# prj3.net
KiCad netlist of a schematic drawn in EAGLE
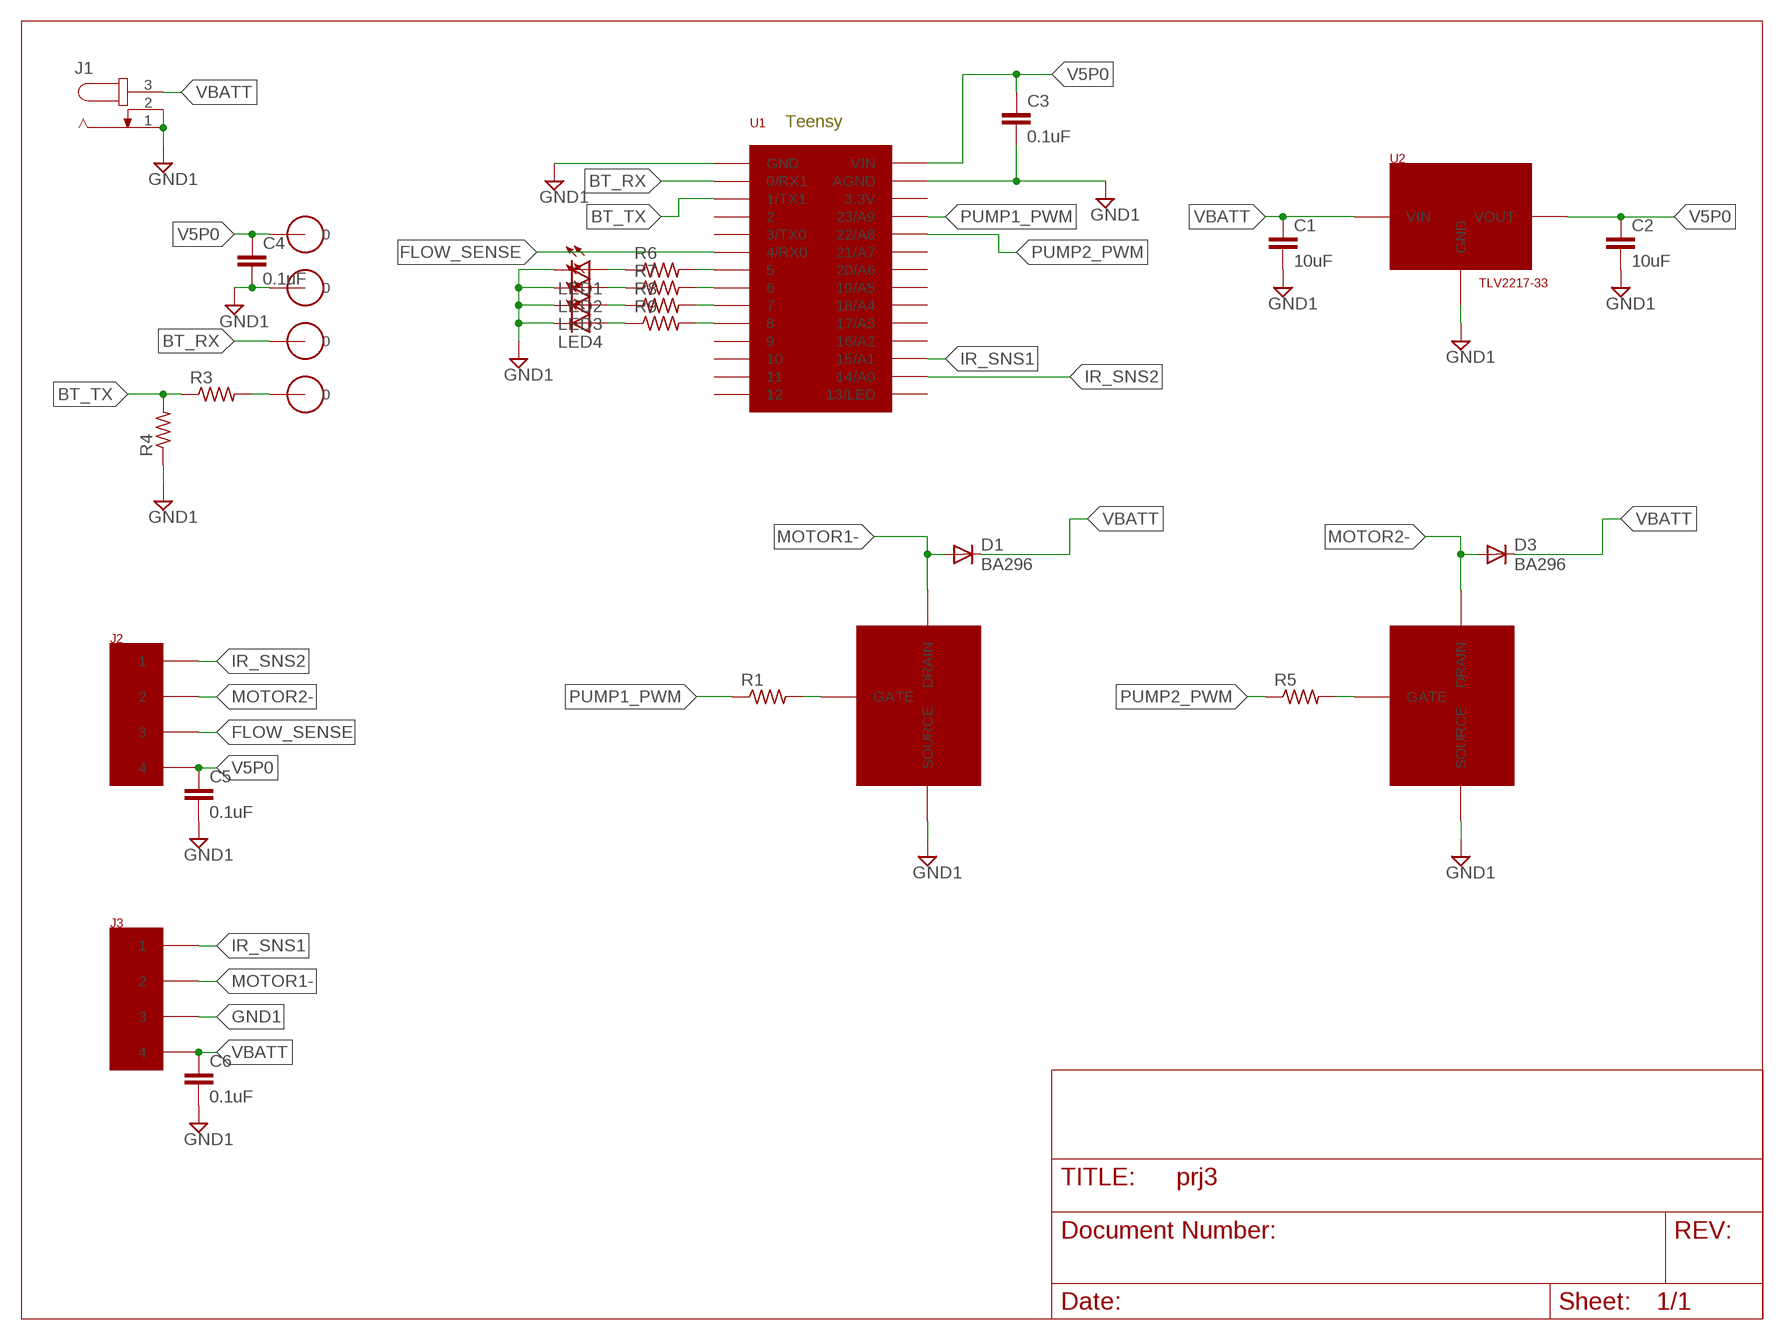
[diagram p0: schematic, sheet 1]

(export (version "E")
  (design (tool "Eeschema 10.0.6"))
  (components
    (comp (ref "C1")
      (value "10uF")
      (footprint "eagle-import:C2.5-3")
      (libsource (lib "eagle-import") (part "C2,5-3"))
    )
    (comp (ref "C2")
      (value "10uF")
      (footprint "eagle-import:C2.5-3")
      (libsource (lib "eagle-import") (part "C2,5-3"))
    )
    (comp (ref "C3")
      (value "0.1uF")
      (footprint "eagle-import:C2.5-3")
      (libsource (lib "eagle-import") (part "C2,5-3"))
    )
    (comp (ref "C4")
      (value "0.1uF")
      (footprint "eagle-import:C2.5-3")
      (libsource (lib "eagle-import") (part "C2,5-3"))
    )
    (comp (ref "C5")
      (value "0.1uF")
      (footprint "eagle-import:C2.5-3")
      (libsource (lib "eagle-import") (part "C2,5-3"))
    )
    (comp (ref "C6")
      (value "0.1uF")
      (footprint "eagle-import:C2.5-3")
      (libsource (lib "eagle-import") (part "C2,5-3"))
    )
    (comp (ref "D1")
      (value "BA296")
      (footprint "eagle-import:P2-15")
      (libsource (lib "eagle-import") (part "BA296"))
    )
    (comp (ref "D3")
      (value "BA296")
      (footprint "eagle-import:P2-15")
      (libsource (lib "eagle-import") (part "BA296"))
    )
    (comp (ref "J1")
      (value "JACK-PLUG0")
      (footprint "eagle-import:SPC4077")
      (libsource (lib "eagle-import") (part "JACK-PLUG0"))
    )
    (comp (ref "J2")
      (value "1776119-4")
      (footprint "eagle-import:4P_SCREW_TERMINAL")
      (libsource (lib "eagle-import") (part "1776119-4"))
    )
    (comp (ref "J3")
      (value "1776119-4")
      (footprint "eagle-import:4P_SCREW_TERMINAL")
      (libsource (lib "eagle-import") (part "1776119-4"))
    )
    (comp (ref "J7")
      (value "35MIL_HOLE")
      (footprint "eagle-import:35MIL_HOLE")
      (libsource (lib "eagle-import") (part "35MIL_HOLE"))
    )
    (comp (ref "J8")
      (value "35MIL_HOLE")
      (footprint "eagle-import:35MIL_HOLE")
      (libsource (lib "eagle-import") (part "35MIL_HOLE"))
    )
    (comp (ref "J9")
      (value "35MIL_HOLE")
      (footprint "eagle-import:35MIL_HOLE")
      (libsource (lib "eagle-import") (part "35MIL_HOLE"))
    )
    (comp (ref "J10")
      (value "35MIL_HOLE")
      (footprint "eagle-import:35MIL_HOLE")
      (libsource (lib "eagle-import") (part "35MIL_HOLE"))
    )
    (comp (ref "LED1")
      (value "LED_ELD260")
      (footprint "eagle-import:LED_LD260")
      (libsource (lib "eagle-import") (part "LED_ELD260"))
    )
    (comp (ref "LED2")
      (value "LED_ELD260")
      (footprint "eagle-import:LED_LD260")
      (libsource (lib "eagle-import") (part "LED_ELD260"))
    )
    (comp (ref "LED3")
      (value "LED_ELD260")
      (footprint "eagle-import:LED_LD260")
      (libsource (lib "eagle-import") (part "LED_ELD260"))
    )
    (comp (ref "LED4")
      (value "LED_ELD260")
      (footprint "eagle-import:LED_LD260")
      (libsource (lib "eagle-import") (part "LED_ELD260"))
    )
    (comp (ref "R1")
      (value "R-US_0207/10")
      (footprint "eagle-import:0207_10")
      (libsource (lib "eagle-import") (part "R-US_0207/10"))
    )
    (comp (ref "R3")
      (value "R-US_0207/10")
      (footprint "eagle-import:0207_10")
      (libsource (lib "eagle-import") (part "R-US_0207/10"))
    )
    (comp (ref "R4")
      (value "R-US_0207/10")
      (footprint "eagle-import:0207_10")
      (libsource (lib "eagle-import") (part "R-US_0207/10"))
    )
    (comp (ref "R5")
      (value "R-US_0207/10")
      (footprint "eagle-import:0207_10")
      (libsource (lib "eagle-import") (part "R-US_0207/10"))
    )
    (comp (ref "R6")
      (value "R-US_0207/10")
      (footprint "eagle-import:0207_10")
      (libsource (lib "eagle-import") (part "R-US_0207/10"))
    )
    (comp (ref "R7")
      (value "R-US_0207/10")
      (footprint "eagle-import:0207_10")
      (libsource (lib "eagle-import") (part "R-US_0207/10"))
    )
    (comp (ref "R8")
      (value "R-US_0207/10")
      (footprint "eagle-import:0207_10")
      (libsource (lib "eagle-import") (part "R-US_0207/10"))
    )
    (comp (ref "R9")
      (value "R-US_0207/10")
      (footprint "eagle-import:0207_10")
      (libsource (lib "eagle-import") (part "R-US_0207/10"))
    )
    (comp (ref "U$2")
      (value "NFET")
      (footprint "eagle-import:TO-220")
      (libsource (lib "eagle-import") (part "NFET"))
    )
    (comp (ref "U$3")
      (value "NFET")
      (footprint "eagle-import:TO-220")
      (libsource (lib "eagle-import") (part "NFET"))
    )
    (comp (ref "U1")
      (value "TEENSY")
      (footprint "eagle-import:TEENSY")
      (libsource (lib "eagle-import") (part "TEENSY"))
    )
    (comp (ref "U2")
      (value "TLV2217-33")
      (footprint "eagle-import:TO-220")
      (libsource (lib "eagle-import") (part "TLV2217-33"))
    )
  )
  (nets
    (net (code "1") (name "BT_RX") (class "Default")
      (node (ref "J9") (pin "P$1") (pinfunction "0_P$1") (pintype "bidirectional"))
      (node (ref "U1") (pin "P$2") (pinfunction "0/RX1_P$2") (pintype "bidirectional"))
    )
    (net (code "2") (name "BT_TX") (class "Default")
      (node (ref "R3") (pin "1") (pinfunction "1_1") (pintype "passive"))
      (node (ref "R4") (pin "2") (pinfunction "2_2") (pintype "passive"))
      (node (ref "U1") (pin "P$3") (pinfunction "1/TX1_P$3") (pintype "bidirectional"))
    )
    (net (code "3") (name "FLOW_SENSE") (class "Default")
      (node (ref "J2") (pin "P$3") (pinfunction "3_P$3") (pintype "bidirectional"))
      (node (ref "U1") (pin "P$6") (pinfunction "4/RX0_P$6") (pintype "bidirectional"))
    )
    (net (code "4") (name "GND1") (class "Default")
      (node (ref "C1") (pin "2") (pinfunction "2_2") (pintype "passive"))
      (node (ref "C2") (pin "2") (pinfunction "2_2") (pintype "passive"))
      (node (ref "C3") (pin "2") (pinfunction "2_2") (pintype "passive"))
      (node (ref "C4") (pin "2") (pinfunction "2_2") (pintype "passive"))
      (node (ref "C5") (pin "2") (pinfunction "2_2") (pintype "passive"))
      (node (ref "C6") (pin "2") (pinfunction "2_2") (pintype "passive"))
      (node (ref "J1") (pin "1") (pinfunction "1_1") (pintype "passive"))
      (node (ref "J1") (pin "2") (pinfunction "2_2") (pintype "passive"))
      (node (ref "J3") (pin "P$3") (pinfunction "3_P$3") (pintype "bidirectional"))
      (node (ref "J8") (pin "P$1") (pinfunction "0_P$1") (pintype "bidirectional"))
      (node (ref "LED1") (pin "K") (pinfunction "C_K") (pintype "passive"))
      (node (ref "LED2") (pin "K") (pinfunction "C_K") (pintype "passive"))
      (node (ref "LED3") (pin "K") (pinfunction "C_K") (pintype "passive"))
      (node (ref "LED4") (pin "K") (pinfunction "C_K") (pintype "passive"))
      (node (ref "R4") (pin "1") (pinfunction "1_1") (pintype "passive"))
      (node (ref "U$2") (pin "3") (pinfunction "SOURCE_3") (pintype "bidirectional"))
      (node (ref "U$3") (pin "3") (pinfunction "SOURCE_3") (pintype "bidirectional"))
      (node (ref "U1") (pin "P$1") (pinfunction "GND_P$1") (pintype "bidirectional"))
      (node (ref "U1") (pin "P$32") (pinfunction "AGND_P$32") (pintype "bidirectional"))
      (node (ref "U2") (pin "2") (pinfunction "GND_2") (pintype "power_in"))
    )
    (net (code "5") (name "IR_SNS1") (class "Default")
      (node (ref "J3") (pin "P$1") (pinfunction "1_P$1") (pintype "bidirectional"))
      (node (ref "U1") (pin "P$22") (pinfunction "15/A1_P$22") (pintype "bidirectional"))
    )
    (net (code "6") (name "IR_SNS2") (class "Default")
      (node (ref "J2") (pin "P$1") (pinfunction "1_P$1") (pintype "bidirectional"))
      (node (ref "U1") (pin "P$21") (pinfunction "14/A0_P$21") (pintype "bidirectional"))
    )
    (net (code "7") (name "MOTOR1-") (class "Default")
      (node (ref "D1") (pin "A") (pinfunction "A_A") (pintype "passive"))
      (node (ref "J3") (pin "P$2") (pinfunction "2_P$2") (pintype "bidirectional"))
      (node (ref "U$2") (pin "2") (pinfunction "DRAIN_2") (pintype "bidirectional"))
    )
    (net (code "8") (name "MOTOR2-") (class "Default")
      (node (ref "D3") (pin "A") (pinfunction "A_A") (pintype "passive"))
      (node (ref "J2") (pin "P$2") (pinfunction "2_P$2") (pintype "bidirectional"))
      (node (ref "U$3") (pin "2") (pinfunction "DRAIN_2") (pintype "bidirectional"))
    )
    (net (code "9") (name "Net-(J10-0)") (class "Default")
      (node (ref "J10") (pin "P$1") (pinfunction "0_P$1") (pintype "bidirectional"))
      (node (ref "R3") (pin "2") (pinfunction "2_2") (pintype "passive"))
    )
    (net (code "10") (name "Net-(LED1-PadA)") (class "Default")
      (node (ref "LED1") (pin "A") (pinfunction "A_A") (pintype "passive"))
      (node (ref "R6") (pin "1") (pinfunction "1_1") (pintype "passive"))
    )
    (net (code "11") (name "Net-(LED2-PadA)") (class "Default")
      (node (ref "LED2") (pin "A") (pinfunction "A_A") (pintype "passive"))
      (node (ref "R7") (pin "1") (pinfunction "1_1") (pintype "passive"))
    )
    (net (code "12") (name "Net-(LED3-PadA)") (class "Default")
      (node (ref "LED3") (pin "A") (pinfunction "A_A") (pintype "passive"))
      (node (ref "R8") (pin "1") (pinfunction "1_1") (pintype "passive"))
    )
    (net (code "13") (name "Net-(LED4-PadA)") (class "Default")
      (node (ref "LED4") (pin "A") (pinfunction "A_A") (pintype "passive"))
      (node (ref "R9") (pin "1") (pinfunction "1_1") (pintype "passive"))
    )
    (net (code "14") (name "Net-(U$2-GATE)") (class "Default")
      (node (ref "R1") (pin "2") (pinfunction "2_2") (pintype "passive"))
      (node (ref "U$2") (pin "1") (pinfunction "GATE_1") (pintype "bidirectional"))
    )
    (net (code "15") (name "Net-(U$3-GATE)") (class "Default")
      (node (ref "R5") (pin "2") (pinfunction "2_2") (pintype "passive"))
      (node (ref "U$3") (pin "1") (pinfunction "GATE_1") (pintype "bidirectional"))
    )
    (net (code "16") (name "Net-(U1-5)") (class "Default")
      (node (ref "R6") (pin "2") (pinfunction "2_2") (pintype "passive"))
      (node (ref "U1") (pin "P$7") (pinfunction "5_P$7") (pintype "bidirectional"))
    )
    (net (code "17") (name "Net-(U1-6)") (class "Default")
      (node (ref "R7") (pin "2") (pinfunction "2_2") (pintype "passive"))
      (node (ref "U1") (pin "P$8") (pinfunction "6_P$8") (pintype "bidirectional"))
    )
    (net (code "18") (name "Net-(U1-7)") (class "Default")
      (node (ref "R8") (pin "2") (pinfunction "2_2") (pintype "passive"))
      (node (ref "U1") (pin "P$9") (pinfunction "7_P$9") (pintype "bidirectional"))
    )
    (net (code "19") (name "Net-(U1-8)") (class "Default")
      (node (ref "R9") (pin "2") (pinfunction "2_2") (pintype "passive"))
      (node (ref "U1") (pin "P$10") (pinfunction "8_P$10") (pintype "bidirectional"))
    )
    (net (code "20") (name "PUMP1_PWM") (class "Default")
      (node (ref "R1") (pin "1") (pinfunction "1_1") (pintype "passive"))
      (node (ref "U1") (pin "P$30") (pinfunction "23/A9_P$30") (pintype "bidirectional"))
    )
    (net (code "21") (name "PUMP2_PWM") (class "Default")
      (node (ref "R5") (pin "1") (pinfunction "1_1") (pintype "passive"))
      (node (ref "U1") (pin "P$29") (pinfunction "22/A8_P$29") (pintype "bidirectional"))
    )
    (net (code "22") (name "V5P0") (class "Default")
      (node (ref "C2") (pin "1") (pinfunction "1_1") (pintype "passive"))
      (node (ref "C3") (pin "1") (pinfunction "1_1") (pintype "passive"))
      (node (ref "C4") (pin "1") (pinfunction "1_1") (pintype "passive"))
      (node (ref "C5") (pin "1") (pinfunction "1_1") (pintype "passive"))
      (node (ref "J2") (pin "P$4") (pinfunction "4_P$4") (pintype "bidirectional"))
      (node (ref "J7") (pin "P$1") (pinfunction "0_P$1") (pintype "bidirectional"))
      (node (ref "U1") (pin "P$33") (pinfunction "VIN_P$33") (pintype "bidirectional"))
      (node (ref "U2") (pin "3") (pinfunction "VOUT_3") (pintype "output"))
    )
    (net (code "23") (name "VBATT") (class "Default")
      (node (ref "C1") (pin "1") (pinfunction "1_1") (pintype "passive"))
      (node (ref "C6") (pin "1") (pinfunction "1_1") (pintype "passive"))
      (node (ref "D1") (pin "C") (pinfunction "C_C") (pintype "passive"))
      (node (ref "D3") (pin "C") (pinfunction "C_C") (pintype "passive"))
      (node (ref "J1") (pin "3") (pinfunction "3_3") (pintype "passive"))
      (node (ref "J3") (pin "P$4") (pinfunction "4_P$4") (pintype "bidirectional"))
      (node (ref "U2") (pin "1") (pinfunction "VIN_1") (pintype "input"))
    )
    (net (code "24") (name "unconnected-(U1-2-PadP$4)") (class "Default")
      (node (ref "U1") (pin "P$4") (pinfunction "2_P$4") (pintype "bidirectional"))
    )
    (net (code "25") (name "unconnected-(U1-3.3V-PadP$31)") (class "Default")
      (node (ref "U1") (pin "P$31") (pinfunction "3.3V_P$31") (pintype "bidirectional"))
    )
    (net (code "26") (name "unconnected-(U1-3{slash}TX0-PadP$5)") (class "Default")
      (node (ref "U1") (pin "P$5") (pinfunction "3/TX0_P$5") (pintype "bidirectional"))
    )
    (net (code "27") (name "unconnected-(U1-9-PadP$11)") (class "Default")
      (node (ref "U1") (pin "P$11") (pinfunction "9_P$11") (pintype "bidirectional"))
    )
    (net (code "28") (name "unconnected-(U1-10-PadP$12)") (class "Default")
      (node (ref "U1") (pin "P$12") (pinfunction "10_P$12") (pintype "bidirectional"))
    )
    (net (code "29") (name "unconnected-(U1-11-PadP$13)") (class "Default")
      (node (ref "U1") (pin "P$13") (pinfunction "11_P$13") (pintype "bidirectional"))
    )
    (net (code "30") (name "unconnected-(U1-12-PadP$14)") (class "Default")
      (node (ref "U1") (pin "P$14") (pinfunction "12_P$14") (pintype "bidirectional"))
    )
    (net (code "31") (name "unconnected-(U1-13{slash}LED-PadP$20)") (class "Default")
      (node (ref "U1") (pin "P$20") (pinfunction "13/LED_P$20") (pintype "bidirectional"))
    )
    (net (code "32") (name "unconnected-(U1-16{slash}A2-PadP$23)") (class "Default")
      (node (ref "U1") (pin "P$23") (pinfunction "16/A2_P$23") (pintype "bidirectional"))
    )
    (net (code "33") (name "unconnected-(U1-17{slash}A3-PadP$24)") (class "Default")
      (node (ref "U1") (pin "P$24") (pinfunction "17/A3_P$24") (pintype "bidirectional"))
    )
    (net (code "34") (name "unconnected-(U1-18{slash}A4-PadP$25)") (class "Default")
      (node (ref "U1") (pin "P$25") (pinfunction "18/A4_P$25") (pintype "bidirectional"))
    )
    (net (code "35") (name "unconnected-(U1-19{slash}A5-PadP$26)") (class "Default")
      (node (ref "U1") (pin "P$26") (pinfunction "19/A5_P$26") (pintype "bidirectional"))
    )
    (net (code "36") (name "unconnected-(U1-20{slash}A6-PadP$27)") (class "Default")
      (node (ref "U1") (pin "P$27") (pinfunction "20/A6_P$27") (pintype "bidirectional"))
    )
    (net (code "37") (name "unconnected-(U1-21{slash}A7-PadP$28)") (class "Default")
      (node (ref "U1") (pin "P$28") (pinfunction "21/A7_P$28") (pintype "bidirectional"))
    )
  )
)
